# USB-LPC-Programmer_modular_V3_7.net
KiCad netlist of a schematic drawn in EAGLE
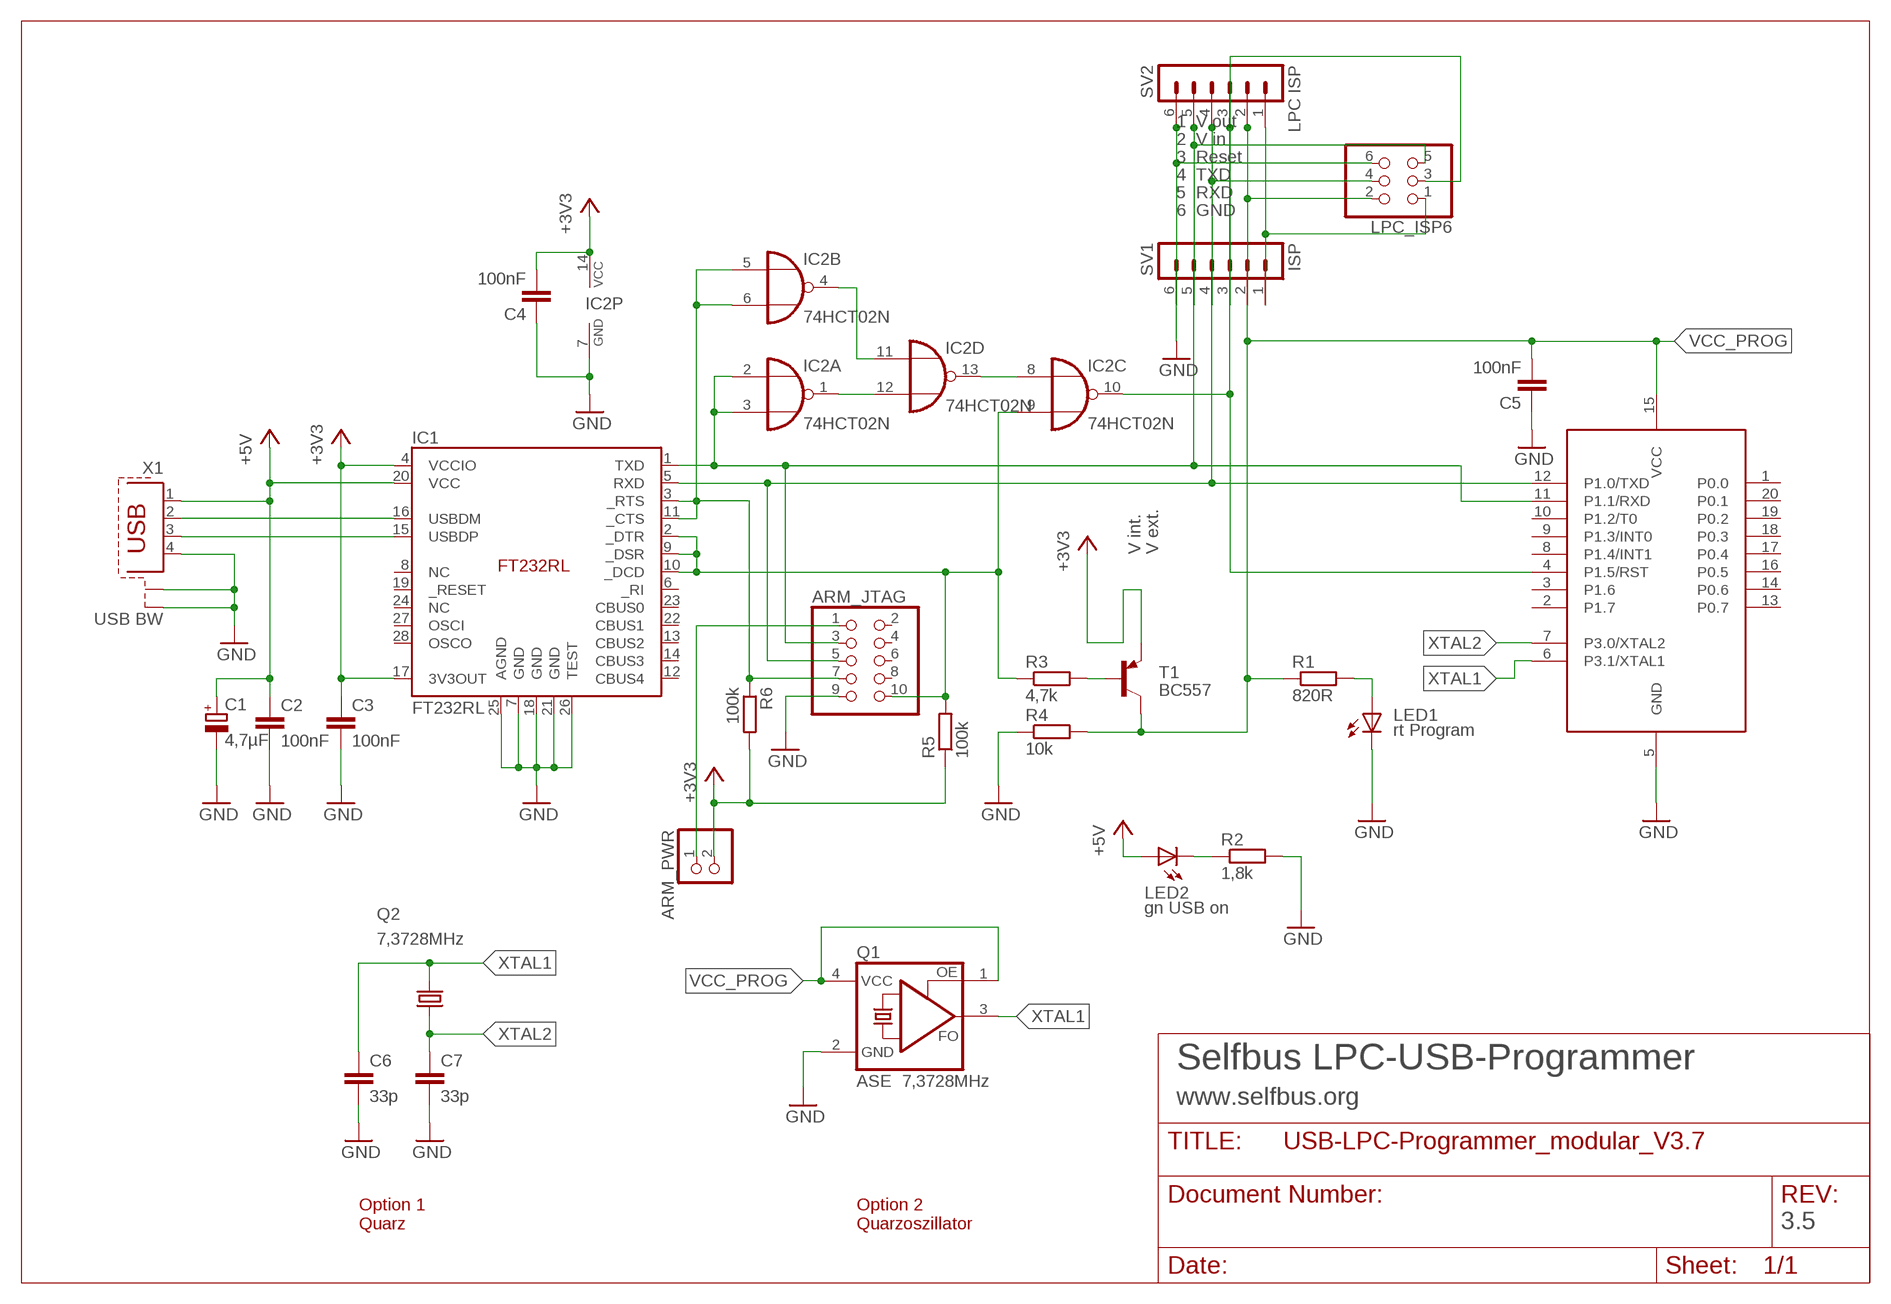
[diagram p0: schematic, sheet 1]

(export (version "E")
  (design (tool "Eeschema 10.0.6"))
  (components
    (comp (ref "89LPC922")
      (value "LPC-Sockel")
      (footprint "eagle-import:DIL20")
      (libsource (lib "eagle-import") (part "89LPC922"))
    )
    (comp (ref "ARM_JTAG")
      (value "PINHD-2X05_2.00")
      (footprint "eagle-import:2X05M")
      (libsource (lib "eagle-import") (part "PINHD-2X05_2.00"))
    )
    (comp (ref "ARM_PWR")
      (value "PINHD-1X02_2.54-S")
      (footprint "eagle-import:1X02-S")
      (libsource (lib "eagle-import") (part "PINHD-1X02_2.54-S"))
    )
    (comp (ref "C1")
      (value "4,7µF")
      (footprint "eagle-import:E2,5-6")
      (libsource (lib "eagle-import") (part "CPOL-EUE2.5-6"))
    )
    (comp (ref "C2")
      (value "100nF")
      (footprint "eagle-import:C025-025X050")
      (libsource (lib "eagle-import") (part "C-EU025-025X050"))
    )
    (comp (ref "C3")
      (value "100nF")
      (footprint "eagle-import:C050-024X044")
      (libsource (lib "eagle-import") (part "C-EU050-024X044"))
    )
    (comp (ref "C4")
      (value "100nF")
      (footprint "eagle-import:C050-024X044")
      (libsource (lib "eagle-import") (part "C-EU050-024X044"))
    )
    (comp (ref "C5")
      (value "100nF")
      (footprint "eagle-import:C050-024X044")
      (libsource (lib "eagle-import") (part "C-EU050-024X044"))
    )
    (comp (ref "C6")
      (value "33p")
      (footprint "eagle-import:C025-024X044")
      (libsource (lib "eagle-import") (part "C-EU025-024X044"))
    )
    (comp (ref "C7")
      (value "33p")
      (footprint "eagle-import:C025-024X044")
      (libsource (lib "eagle-import") (part "C-EU025-024X044"))
    )
    (comp (ref "IC1")
      (value "FT232RL")
      (footprint "eagle-import:SSOP-28")
      (libsource (lib "eagle-import") (part "FT232RL"))
    )
    (comp (ref "IC2")
      (value "74HCT02N")
      (footprint "eagle-import:DIL14")
      (libsource (lib "eagle-import") (part "7402NHCT"))
    )
    (comp (ref "LED1")
      (value "rt Program")
      (footprint "eagle-import:LED3MM")
      (libsource (lib "eagle-import") (part "LED3MM"))
    )
    (comp (ref "LED2")
      (value "gn USB on")
      (footprint "eagle-import:LED3MM")
      (libsource (lib "eagle-import") (part "LED3MM"))
    )
    (comp (ref "LPC_ISP6")
      (value "PINHD-2X3")
      (footprint "eagle-import:2X03")
      (libsource (lib "eagle-import") (part "PINHD-2X3"))
    )
    (comp (ref "Q1")
      (value "ASE 7,3728MHz")
      (footprint "eagle-import:ASF")
      (libsource (lib "eagle-import") (part "ASF1"))
    )
    (comp (ref "Q2")
      (value "7,3728MHz")
      (footprint "eagle-import:HC49_S")
      (libsource (lib "eagle-import") (part "CRYSTALHC49S"))
    )
    (comp (ref "R1")
      (value "820R")
      (footprint "eagle-import:0207_7")
      (libsource (lib "eagle-import") (part "R-EU_0207/7"))
    )
    (comp (ref "R2")
      (value "1,8k")
      (footprint "eagle-import:0207_7")
      (libsource (lib "eagle-import") (part "R-EU_0207/7"))
    )
    (comp (ref "R3")
      (value "4,7k")
      (footprint "eagle-import:0204_7")
      (libsource (lib "eagle-import") (part "R-EU_0204/7"))
    )
    (comp (ref "R4")
      (value "10k")
      (footprint "eagle-import:0207_7")
      (libsource (lib "eagle-import") (part "R-EU_0207/7"))
    )
    (comp (ref "R5")
      (value "100k")
      (footprint "eagle-import:0207_7")
      (libsource (lib "eagle-import") (part "R-EU_0207/7"))
    )
    (comp (ref "R6")
      (value "100k")
      (footprint "eagle-import:0207_7")
      (libsource (lib "eagle-import") (part "R-EU_0207/7"))
    )
    (comp (ref "SV1")
      (value "ISP")
      (footprint "eagle-import:MA06-1")
      (libsource (lib "eagle-import") (part "MA06-1"))
    )
    (comp (ref "SV2")
      (value "LPC ISP")
      (footprint "eagle-import:MA06-1")
      (fields (field (name "OC_FARNELL") "unknown") (field (name "OC_NEWARK") "unknown"))
      (libsource (lib "eagle-import") (part "MA06-1"))
    )
    (comp (ref "T1")
      (value "BC557")
      (footprint "eagle-import:TO92")
      (libsource (lib "eagle-import") (part "BC557"))
    )
    (comp (ref "X1")
      (value "USB BW")
      (footprint "eagle-import:PN61729-S")
      (libsource (lib "eagle-import") (part "PN61729-S"))
    )
  )
  (nets
    (net (code "1") (name "+3V3") (class "Default")
      (node (ref "ARM_PWR") (pin "2") (pinfunction "2_2") (pintype "passive"))
      (node (ref "C3") (pin "1") (pinfunction "1_1") (pintype "passive"))
      (node (ref "C4") (pin "2") (pinfunction "2_2") (pintype "passive"))
      (node (ref "IC1") (pin "17") (pinfunction "3V3OUT_17") (pintype "output"))
      (node (ref "IC1") (pin "4") (pinfunction "VCCIO_4") (pintype "power_in"))
      (node (ref "IC2") (pin "14") (pinfunction "VCC_14") (pintype "power_in"))
      (node (ref "R5") (pin "1") (pinfunction "1_1") (pintype "passive"))
      (node (ref "R6") (pin "2") (pinfunction "2_2") (pintype "passive"))
      (node (ref "T1") (pin "1") (pinfunction "E_1") (pintype "passive"))
    )
    (net (code "2") (name "+5V") (class "Default")
      (node (ref "C1") (pin "+") (pinfunction "+_+") (pintype "passive"))
      (node (ref "C2") (pin "1") (pinfunction "1_1") (pintype "passive"))
      (node (ref "IC1") (pin "20") (pinfunction "VCC_20") (pintype "power_in"))
      (node (ref "LED2") (pin "A") (pinfunction "A_A") (pintype "passive"))
      (node (ref "X1") (pin "1") (pinfunction "1_1") (pintype "passive"))
    )
    (net (code "3") (name "GND") (class "Default")
      (node (ref "89LPC922") (pin "5") (pinfunction "GND_5") (pintype "bidirectional"))
      (node (ref "ARM_JTAG") (pin "9") (pinfunction "9_9") (pintype "passive"))
      (node (ref "C1") (pin "-") (pinfunction "-_-") (pintype "passive"))
      (node (ref "C2") (pin "2") (pinfunction "2_2") (pintype "passive"))
      (node (ref "C3") (pin "2") (pinfunction "2_2") (pintype "passive"))
      (node (ref "C4") (pin "1") (pinfunction "1_1") (pintype "passive"))
      (node (ref "C5") (pin "1") (pinfunction "1_1") (pintype "passive"))
      (node (ref "C6") (pin "2") (pinfunction "2_2") (pintype "passive"))
      (node (ref "C7") (pin "2") (pinfunction "2_2") (pintype "passive"))
      (node (ref "IC1") (pin "18") (pinfunction "GND_18") (pintype "power_in"))
      (node (ref "IC1") (pin "21") (pinfunction "GND_21") (pintype "power_in"))
      (node (ref "IC1") (pin "25") (pinfunction "AGND_25") (pintype "power_in"))
      (node (ref "IC1") (pin "26") (pinfunction "TEST_26") (pintype "bidirectional"))
      (node (ref "IC1") (pin "7") (pinfunction "GND_7") (pintype "power_in"))
      (node (ref "IC2") (pin "7") (pinfunction "GND_7") (pintype "power_in"))
      (node (ref "LED1") (pin "K") (pinfunction "C_K") (pintype "passive"))
      (node (ref "LPC_ISP6") (pin "6") (pinfunction "6_6") (pintype "passive"))
      (node (ref "Q1") (pin "2") (pinfunction "GND_2") (pintype "power_in"))
      (node (ref "R2") (pin "2") (pinfunction "2_2") (pintype "passive"))
      (node (ref "R4") (pin "1") (pinfunction "1_1") (pintype "passive"))
      (node (ref "SV1") (pin "6") (pinfunction "6_6") (pintype "passive"))
      (node (ref "SV2") (pin "6") (pinfunction "6_6") (pintype "passive"))
      (node (ref "X1") (pin "4") (pinfunction "4_4") (pintype "passive"))
      (node (ref "X1") (pin "S1") (pinfunction "S1_S1") (pintype "passive"))
      (node (ref "X1") (pin "S2") (pinfunction "S2_S2") (pintype "passive"))
    )
    (net (code "4") (name "Net-(89LPC922-P1.0{slash}TXD)") (class "Default")
      (node (ref "89LPC922") (pin "12") (pinfunction "P1.0/TXD_12") (pintype "bidirectional"))
      (node (ref "ARM_JTAG") (pin "5") (pinfunction "5_5") (pintype "passive"))
      (node (ref "IC1") (pin "5") (pinfunction "RXD_5") (pintype "input"))
      (node (ref "LPC_ISP6") (pin "4") (pinfunction "4_4") (pintype "passive"))
      (node (ref "SV1") (pin "4") (pinfunction "4_4") (pintype "passive"))
      (node (ref "SV2") (pin "4") (pinfunction "4_4") (pintype "passive"))
    )
    (net (code "5") (name "Net-(89LPC922-P1.1{slash}RXD)") (class "Default")
      (node (ref "89LPC922") (pin "11") (pinfunction "P1.1/RXD_11") (pintype "bidirectional"))
      (node (ref "ARM_JTAG") (pin "3") (pinfunction "3_3") (pintype "passive"))
      (node (ref "IC1") (pin "1") (pinfunction "TXD_1") (pintype "output"))
      (node (ref "IC2") (pin "2") (pinfunction "I0_2") (pintype "input"))
      (node (ref "IC2") (pin "3") (pinfunction "I1_3") (pintype "input"))
      (node (ref "LPC_ISP6") (pin "5") (pinfunction "5_5") (pintype "passive"))
      (node (ref "SV1") (pin "5") (pinfunction "5_5") (pintype "passive"))
      (node (ref "SV2") (pin "5") (pinfunction "5_5") (pintype "passive"))
    )
    (net (code "6") (name "Net-(89LPC922-P1.5{slash}RST)") (class "Default")
      (node (ref "89LPC922") (pin "4") (pinfunction "P1.5/RST_4") (pintype "bidirectional"))
      (node (ref "IC2") (pin "10") (pinfunction "O_10") (pintype "output"))
      (node (ref "LPC_ISP6") (pin "3") (pinfunction "3_3") (pintype "passive"))
      (node (ref "SV1") (pin "3") (pinfunction "3_3") (pintype "passive"))
      (node (ref "SV2") (pin "3") (pinfunction "3_3") (pintype "passive"))
    )
    (net (code "7") (name "Net-(ARM_JTAG-Pad1)") (class "Default")
      (node (ref "ARM_JTAG") (pin "1") (pinfunction "1_1") (pintype "passive"))
      (node (ref "ARM_PWR") (pin "1") (pinfunction "1_1") (pintype "passive"))
    )
    (net (code "8") (name "Net-(IC1-USBDM)") (class "Default")
      (node (ref "IC1") (pin "16") (pinfunction "USBDM_16") (pintype "bidirectional"))
      (node (ref "X1") (pin "2") (pinfunction "2_2") (pintype "passive"))
    )
    (net (code "9") (name "Net-(IC1-USBDP)") (class "Default")
      (node (ref "IC1") (pin "15") (pinfunction "USBDP_15") (pintype "bidirectional"))
      (node (ref "X1") (pin "3") (pinfunction "3_3") (pintype "passive"))
    )
    (net (code "10") (name "Net-(IC1-_CTS)") (class "Default")
      (node (ref "ARM_JTAG") (pin "7") (pinfunction "7_7") (pintype "passive"))
      (node (ref "IC1") (pin "11") (pinfunction "_CTS_11") (pintype "input"))
      (node (ref "IC1") (pin "3") (pinfunction "_RTS_3") (pintype "output"))
      (node (ref "IC2") (pin "5") (pinfunction "I0_5") (pintype "input"))
      (node (ref "IC2") (pin "6") (pinfunction "I1_6") (pintype "input"))
      (node (ref "R6") (pin "1") (pinfunction "1_1") (pintype "passive"))
    )
    (net (code "11") (name "Net-(IC1-_DCD)") (class "Default")
      (node (ref "ARM_JTAG") (pin "10") (pinfunction "10_10") (pintype "passive"))
      (node (ref "IC1") (pin "10") (pinfunction "_DCD_10") (pintype "input"))
      (node (ref "IC1") (pin "2") (pinfunction "_DTR_2") (pintype "input"))
      (node (ref "IC1") (pin "9") (pinfunction "_DSR_9") (pintype "input"))
      (node (ref "IC2") (pin "9") (pinfunction "I1_9") (pintype "input"))
      (node (ref "R3") (pin "1") (pinfunction "1_1") (pintype "passive"))
      (node (ref "R5") (pin "2") (pinfunction "2_2") (pintype "passive"))
    )
    (net (code "12") (name "Net-(IC2A-O)") (class "Default")
      (node (ref "IC2") (pin "1") (pinfunction "O_1") (pintype "output"))
      (node (ref "IC2") (pin "12") (pinfunction "I1_12") (pintype "input"))
    )
    (net (code "13") (name "Net-(IC2B-O)") (class "Default")
      (node (ref "IC2") (pin "11") (pinfunction "I0_11") (pintype "input"))
      (node (ref "IC2") (pin "4") (pinfunction "O_4") (pintype "output"))
    )
    (net (code "14") (name "Net-(IC2C-I0)") (class "Default")
      (node (ref "IC2") (pin "13") (pinfunction "O_13") (pintype "output"))
      (node (ref "IC2") (pin "8") (pinfunction "I0_8") (pintype "input"))
    )
    (net (code "15") (name "Net-(LED1-PadA)") (class "Default")
      (node (ref "LED1") (pin "A") (pinfunction "A_A") (pintype "passive"))
      (node (ref "R1") (pin "2") (pinfunction "2_2") (pintype "passive"))
    )
    (net (code "16") (name "Net-(LED2-C)") (class "Default")
      (node (ref "LED2") (pin "K") (pinfunction "C_K") (pintype "passive"))
      (node (ref "R2") (pin "1") (pinfunction "1_1") (pintype "passive"))
    )
    (net (code "17") (name "Net-(LPC_ISP6-Pad1)") (class "Default")
      (node (ref "LPC_ISP6") (pin "1") (pinfunction "1_1") (pintype "passive"))
      (node (ref "SV1") (pin "1") (pinfunction "1_1") (pintype "passive"))
      (node (ref "SV2") (pin "1") (pinfunction "1_1") (pintype "passive"))
    )
    (net (code "18") (name "Net-(T1-B)") (class "Default")
      (node (ref "R3") (pin "2") (pinfunction "2_2") (pintype "passive"))
      (node (ref "T1") (pin "2") (pinfunction "B_2") (pintype "passive"))
    )
    (net (code "19") (name "VCC_PROG") (class "Default")
      (node (ref "89LPC922") (pin "15") (pinfunction "VCC_15") (pintype "bidirectional"))
      (node (ref "C5") (pin "2") (pinfunction "2_2") (pintype "passive"))
      (node (ref "LPC_ISP6") (pin "2") (pinfunction "2_2") (pintype "passive"))
      (node (ref "Q1") (pin "1") (pinfunction "OE_1") (pintype "input"))
      (node (ref "Q1") (pin "4") (pinfunction "VCC_4") (pintype "power_in"))
      (node (ref "R1") (pin "1") (pinfunction "1_1") (pintype "passive"))
      (node (ref "R4") (pin "2") (pinfunction "2_2") (pintype "passive"))
      (node (ref "SV1") (pin "2") (pinfunction "2_2") (pintype "passive"))
      (node (ref "SV2") (pin "2") (pinfunction "2_2") (pintype "passive"))
      (node (ref "T1") (pin "3") (pinfunction "C_3") (pintype "passive"))
    )
    (net (code "20") (name "XTAL1") (class "Default")
      (node (ref "89LPC922") (pin "6") (pinfunction "P3.1/XTAL1_6") (pintype "bidirectional"))
      (node (ref "C6") (pin "1") (pinfunction "1_1") (pintype "passive"))
      (node (ref "Q1") (pin "3") (pinfunction "FO_3") (pintype "output"))
      (node (ref "Q2") (pin "2") (pinfunction "2_2") (pintype "passive"))
    )
    (net (code "21") (name "XTAL2") (class "Default")
      (node (ref "89LPC922") (pin "7") (pinfunction "P3.0/XTAL2_7") (pintype "bidirectional"))
      (node (ref "C7") (pin "1") (pinfunction "1_1") (pintype "passive"))
      (node (ref "Q2") (pin "1") (pinfunction "1_1") (pintype "passive"))
    )
    (net (code "22") (name "unconnected-(89LPC922-P0.0-Pad1)") (class "Default")
      (node (ref "89LPC922") (pin "1") (pinfunction "P0.0_1") (pintype "bidirectional"))
    )
    (net (code "23") (name "unconnected-(89LPC922-P0.1-Pad20)") (class "Default")
      (node (ref "89LPC922") (pin "20") (pinfunction "P0.1_20") (pintype "bidirectional"))
    )
    (net (code "24") (name "unconnected-(89LPC922-P0.2-Pad19)") (class "Default")
      (node (ref "89LPC922") (pin "19") (pinfunction "P0.2_19") (pintype "bidirectional"))
    )
    (net (code "25") (name "unconnected-(89LPC922-P0.3-Pad18)") (class "Default")
      (node (ref "89LPC922") (pin "18") (pinfunction "P0.3_18") (pintype "bidirectional"))
    )
    (net (code "26") (name "unconnected-(89LPC922-P0.4-Pad17)") (class "Default")
      (node (ref "89LPC922") (pin "17") (pinfunction "P0.4_17") (pintype "bidirectional"))
    )
    (net (code "27") (name "unconnected-(89LPC922-P0.5-Pad16)") (class "Default")
      (node (ref "89LPC922") (pin "16") (pinfunction "P0.5_16") (pintype "bidirectional"))
    )
    (net (code "28") (name "unconnected-(89LPC922-P0.6-Pad14)") (class "Default")
      (node (ref "89LPC922") (pin "14") (pinfunction "P0.6_14") (pintype "bidirectional"))
    )
    (net (code "29") (name "unconnected-(89LPC922-P0.7-Pad13)") (class "Default")
      (node (ref "89LPC922") (pin "13") (pinfunction "P0.7_13") (pintype "bidirectional"))
    )
    (net (code "30") (name "unconnected-(89LPC922-P1.2{slash}T0-Pad10)") (class "Default")
      (node (ref "89LPC922") (pin "10") (pinfunction "P1.2/T0_10") (pintype "bidirectional"))
    )
    (net (code "31") (name "unconnected-(89LPC922-P1.3{slash}INT0-Pad9)") (class "Default")
      (node (ref "89LPC922") (pin "9") (pinfunction "P1.3/INT0_9") (pintype "bidirectional"))
    )
    (net (code "32") (name "unconnected-(89LPC922-P1.4{slash}INT1-Pad8)") (class "Default")
      (node (ref "89LPC922") (pin "8") (pinfunction "P1.4/INT1_8") (pintype "bidirectional"))
    )
    (net (code "33") (name "unconnected-(89LPC922-P1.6-Pad3)") (class "Default")
      (node (ref "89LPC922") (pin "3") (pinfunction "P1.6_3") (pintype "bidirectional"))
    )
    (net (code "34") (name "unconnected-(89LPC922-P1.7-Pad2)") (class "Default")
      (node (ref "89LPC922") (pin "2") (pinfunction "P1.7_2") (pintype "bidirectional"))
    )
    (net (code "35") (name "unconnected-(ARM_JTAG-Pad2)") (class "Default")
      (node (ref "ARM_JTAG") (pin "2") (pinfunction "2_2") (pintype "passive"))
    )
    (net (code "36") (name "unconnected-(ARM_JTAG-Pad4)") (class "Default")
      (node (ref "ARM_JTAG") (pin "4") (pinfunction "4_4") (pintype "passive"))
    )
    (net (code "37") (name "unconnected-(ARM_JTAG-Pad6)") (class "Default")
      (node (ref "ARM_JTAG") (pin "6") (pinfunction "6_6") (pintype "passive"))
    )
    (net (code "38") (name "unconnected-(ARM_JTAG-Pad8)") (class "Default")
      (node (ref "ARM_JTAG") (pin "8") (pinfunction "8_8") (pintype "passive"))
    )
    (net (code "39") (name "unconnected-(IC1-CBUS0-Pad23)") (class "Default")
      (node (ref "IC1") (pin "23") (pinfunction "CBUS0_23") (pintype "bidirectional"))
    )
    (net (code "40") (name "unconnected-(IC1-CBUS1-Pad22)") (class "Default")
      (node (ref "IC1") (pin "22") (pinfunction "CBUS1_22") (pintype "bidirectional"))
    )
    (net (code "41") (name "unconnected-(IC1-CBUS2-Pad13)") (class "Default")
      (node (ref "IC1") (pin "13") (pinfunction "CBUS2_13") (pintype "bidirectional"))
    )
    (net (code "42") (name "unconnected-(IC1-CBUS3-Pad14)") (class "Default")
      (node (ref "IC1") (pin "14") (pinfunction "CBUS3_14") (pintype "bidirectional"))
    )
    (net (code "43") (name "unconnected-(IC1-CBUS4-Pad12)") (class "Default")
      (node (ref "IC1") (pin "12") (pinfunction "CBUS4_12") (pintype "bidirectional"))
    )
    (net (code "44") (name "unconnected-(IC1-NC-Pad8)") (class "Default")
      (node (ref "IC1") (pin "8") (pinfunction "NC_8") (pintype "no_connect"))
    )
    (net (code "45") (name "unconnected-(IC1-NC-Pad24)") (class "Default")
      (node (ref "IC1") (pin "24") (pinfunction "NC_24") (pintype "no_connect"))
    )
    (net (code "46") (name "unconnected-(IC1-OSCI-Pad27)") (class "Default")
      (node (ref "IC1") (pin "27") (pinfunction "OSCI_27") (pintype "input"))
    )
    (net (code "47") (name "unconnected-(IC1-OSCO-Pad28)") (class "Default")
      (node (ref "IC1") (pin "28") (pinfunction "OSCO_28") (pintype "output"))
    )
    (net (code "48") (name "unconnected-(IC1-_RESET-Pad19)") (class "Default")
      (node (ref "IC1") (pin "19") (pinfunction "_RESET_19") (pintype "input"))
    )
    (net (code "49") (name "unconnected-(IC1-_RI-Pad6)") (class "Default")
      (node (ref "IC1") (pin "6") (pinfunction "_RI_6") (pintype "input"))
    )
  )
)
